# G203B.net
KiCad netlist of a schematic drawn in EAGLE
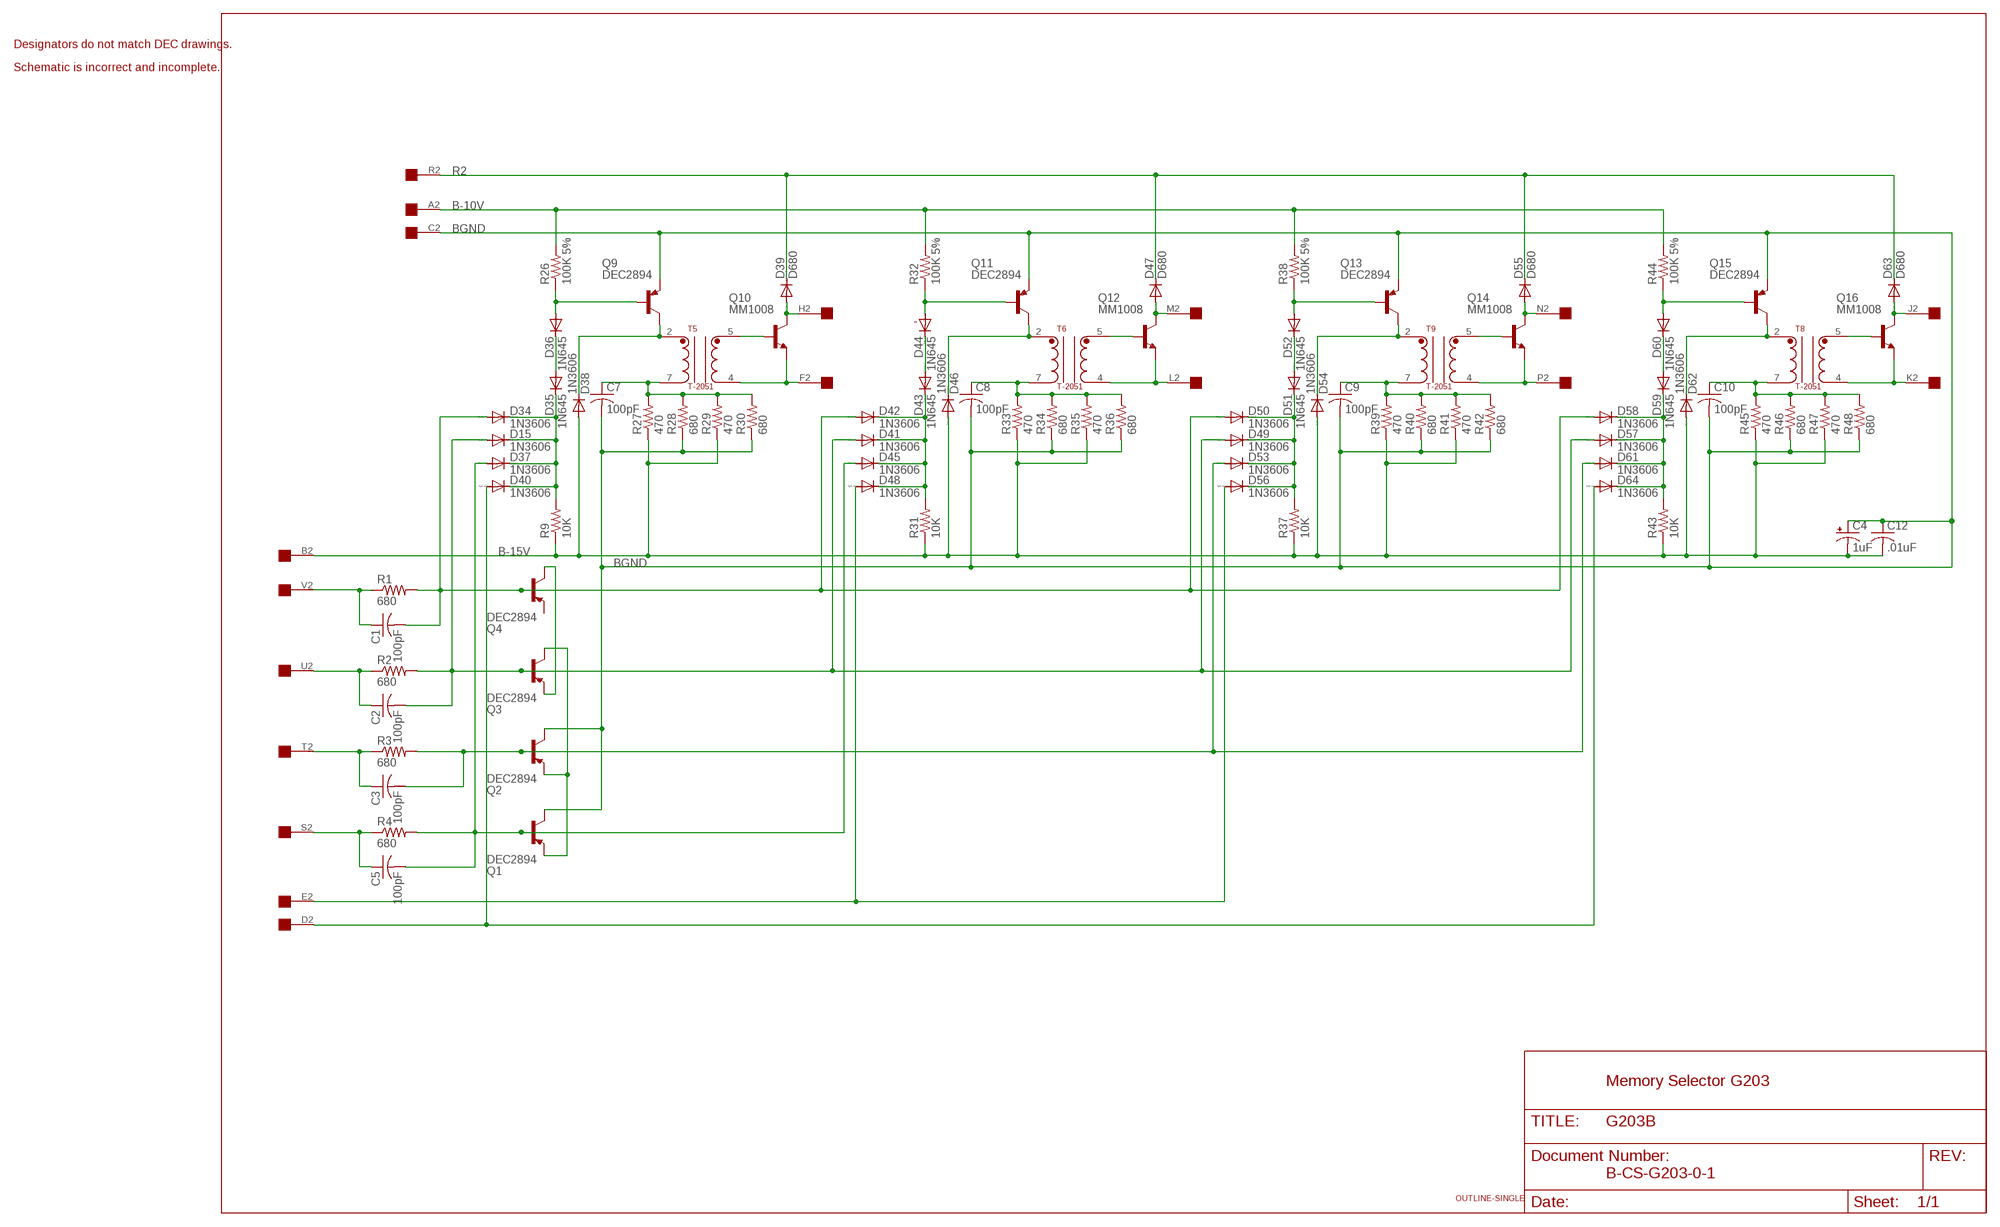
[diagram p0: schematic, sheet 1]

(export (version "E")
  (design (tool "Eeschema 10.0.6"))
  (components
    (comp (ref "C1")
      (value "100pF")
      (footprint "eagle-import:C075-032X103")
      (libsource (lib "eagle-import") (part "C-US075-032X103"))
    )
    (comp (ref "C2")
      (value "100pF")
      (footprint "eagle-import:C075-032X103")
      (libsource (lib "eagle-import") (part "C-US075-032X103"))
    )
    (comp (ref "C3")
      (value "100pF")
      (footprint "eagle-import:C075-032X103")
      (libsource (lib "eagle-import") (part "C-US075-032X103"))
    )
    (comp (ref "C4")
      (value "1uF")
      (footprint "eagle-import:E12-4")
      (libsource (lib "eagle-import") (part "CPOL-USE12-4AXIAL"))
    )
    (comp (ref "C5")
      (value "100pF")
      (footprint "eagle-import:C075-032X103")
      (libsource (lib "eagle-import") (part "C-US075-032X103"))
    )
    (comp (ref "C7")
      (value "100pF")
      (footprint "eagle-import:C075-032X103")
      (libsource (lib "eagle-import") (part "C-US075-032X103"))
    )
    (comp (ref "C8")
      (value "100pF")
      (footprint "eagle-import:C075-032X103")
      (libsource (lib "eagle-import") (part "C-US075-032X103"))
    )
    (comp (ref "C9")
      (value "100pF")
      (footprint "eagle-import:C075-032X103")
      (libsource (lib "eagle-import") (part "C-US075-032X103"))
    )
    (comp (ref "C10")
      (value "100pF")
      (footprint "eagle-import:C075-032X103")
      (libsource (lib "eagle-import") (part "C-US075-032X103"))
    )
    (comp (ref "C12")
      (value ".01uF")
      (footprint "eagle-import:C050-025X075")
      (libsource (lib "eagle-import") (part "C-US050-025X075"))
    )
    (comp (ref "D15")
      (value "1N3606")
      (footprint "eagle-import:DO35-10")
      (libsource (lib "eagle-import") (part "1N4148DO35-10"))
    )
    (comp (ref "D34")
      (value "1N3606")
      (footprint "eagle-import:DO35-10")
      (libsource (lib "eagle-import") (part "1N4148DO35-10"))
    )
    (comp (ref "D35")
      (value "1N645")
      (footprint "eagle-import:DO35-10")
      (libsource (lib "eagle-import") (part "1N4148DO35-10"))
    )
    (comp (ref "D36")
      (value "1N645")
      (footprint "eagle-import:DO35-10")
      (libsource (lib "eagle-import") (part "1N4148DO35-10"))
    )
    (comp (ref "D37")
      (value "1N3606")
      (footprint "eagle-import:DO35-10")
      (libsource (lib "eagle-import") (part "1N4148DO35-10"))
    )
    (comp (ref "D38")
      (value "1N3606")
      (footprint "eagle-import:DO35-10")
      (libsource (lib "eagle-import") (part "1N4148DO35-10"))
    )
    (comp (ref "D39")
      (value "D680")
      (footprint "eagle-import:DO35-10")
      (libsource (lib "eagle-import") (part "1N4148DO35-10"))
    )
    (comp (ref "D40")
      (value "1N3606")
      (footprint "eagle-import:DO35-10")
      (libsource (lib "eagle-import") (part "1N4148DO35-10"))
    )
    (comp (ref "D41")
      (value "1N3606")
      (footprint "eagle-import:DO35-10")
      (libsource (lib "eagle-import") (part "1N4148DO35-10"))
    )
    (comp (ref "D42")
      (value "1N3606")
      (footprint "eagle-import:DO35-10")
      (libsource (lib "eagle-import") (part "1N4148DO35-10"))
    )
    (comp (ref "D43")
      (value "1N645")
      (footprint "eagle-import:DO35-10")
      (libsource (lib "eagle-import") (part "1N4148DO35-10"))
    )
    (comp (ref "D44")
      (value "1N645")
      (footprint "eagle-import:DO35-10")
      (libsource (lib "eagle-import") (part "1N4148DO35-10"))
    )
    (comp (ref "D45")
      (value "1N3606")
      (footprint "eagle-import:DO35-10")
      (libsource (lib "eagle-import") (part "1N4148DO35-10"))
    )
    (comp (ref "D46")
      (value "1N3606")
      (footprint "eagle-import:DO35-10")
      (libsource (lib "eagle-import") (part "1N4148DO35-10"))
    )
    (comp (ref "D47")
      (value "D680")
      (footprint "eagle-import:DO35-10")
      (libsource (lib "eagle-import") (part "1N4148DO35-10"))
    )
    (comp (ref "D48")
      (value "1N3606")
      (footprint "eagle-import:DO35-10")
      (libsource (lib "eagle-import") (part "1N4148DO35-10"))
    )
    (comp (ref "D49")
      (value "1N3606")
      (footprint "eagle-import:DO35-10")
      (libsource (lib "eagle-import") (part "1N4148DO35-10"))
    )
    (comp (ref "D50")
      (value "1N3606")
      (footprint "eagle-import:DO35-10")
      (libsource (lib "eagle-import") (part "1N4148DO35-10"))
    )
    (comp (ref "D51")
      (value "1N645")
      (footprint "eagle-import:DO35-10")
      (libsource (lib "eagle-import") (part "1N4148DO35-10"))
    )
    (comp (ref "D52")
      (value "1N645")
      (footprint "eagle-import:DO35-10")
      (libsource (lib "eagle-import") (part "1N4148DO35-10"))
    )
    (comp (ref "D53")
      (value "1N3606")
      (footprint "eagle-import:DO35-10")
      (libsource (lib "eagle-import") (part "1N4148DO35-10"))
    )
    (comp (ref "D54")
      (value "1N3606")
      (footprint "eagle-import:DO35-10")
      (libsource (lib "eagle-import") (part "1N4148DO35-10"))
    )
    (comp (ref "D55")
      (value "D680")
      (footprint "eagle-import:DO35-10")
      (libsource (lib "eagle-import") (part "1N4148DO35-10"))
    )
    (comp (ref "D56")
      (value "1N3606")
      (footprint "eagle-import:DO35-10")
      (libsource (lib "eagle-import") (part "1N4148DO35-10"))
    )
    (comp (ref "D57")
      (value "1N3606")
      (footprint "eagle-import:DO35-10")
      (libsource (lib "eagle-import") (part "1N4148DO35-10"))
    )
    (comp (ref "D58")
      (value "1N3606")
      (footprint "eagle-import:DO35-10")
      (libsource (lib "eagle-import") (part "1N4148DO35-10"))
    )
    (comp (ref "D59")
      (value "1N645")
      (footprint "eagle-import:DO35-10")
      (libsource (lib "eagle-import") (part "1N4148DO35-10"))
    )
    (comp (ref "D60")
      (value "1N645")
      (footprint "eagle-import:DO35-10")
      (libsource (lib "eagle-import") (part "1N4148DO35-10"))
    )
    (comp (ref "D61")
      (value "1N3606")
      (footprint "eagle-import:DO35-10")
      (libsource (lib "eagle-import") (part "1N4148DO35-10"))
    )
    (comp (ref "D62")
      (value "1N3606")
      (footprint "eagle-import:DO35-10")
      (libsource (lib "eagle-import") (part "1N4148DO35-10"))
    )
    (comp (ref "D63")
      (value "D680")
      (footprint "eagle-import:DO35-10")
      (libsource (lib "eagle-import") (part "1N4148DO35-10"))
    )
    (comp (ref "D64")
      (value "1N3606")
      (footprint "eagle-import:DO35-10")
      (libsource (lib "eagle-import") (part "1N4148DO35-10"))
    )
    (comp (ref "Q1")
      (value "DEC2894")
      (footprint "eagle-import:TO39")
      (libsource (lib "eagle-import") (part "2N2904"))
    )
    (comp (ref "Q2")
      (value "DEC2894")
      (footprint "eagle-import:TO39")
      (libsource (lib "eagle-import") (part "2N2904"))
    )
    (comp (ref "Q3")
      (value "DEC2894")
      (footprint "eagle-import:TO39")
      (libsource (lib "eagle-import") (part "2N2904"))
    )
    (comp (ref "Q4")
      (value "DEC2894")
      (footprint "eagle-import:TO39")
      (libsource (lib "eagle-import") (part "2N2904"))
    )
    (comp (ref "Q9")
      (value "DEC2894")
      (footprint "eagle-import:TO39")
      (libsource (lib "eagle-import") (part "2N2904"))
    )
    (comp (ref "Q10")
      (value "MM1008")
      (footprint "eagle-import:TO5")
      (libsource (lib "eagle-import") (part "2N2102"))
    )
    (comp (ref "Q11")
      (value "DEC2894")
      (footprint "eagle-import:TO39")
      (libsource (lib "eagle-import") (part "2N2904"))
    )
    (comp (ref "Q12")
      (value "MM1008")
      (footprint "eagle-import:TO5")
      (libsource (lib "eagle-import") (part "2N2102"))
    )
    (comp (ref "Q13")
      (value "DEC2894")
      (footprint "eagle-import:TO39")
      (libsource (lib "eagle-import") (part "2N2904"))
    )
    (comp (ref "Q14")
      (value "MM1008")
      (footprint "eagle-import:TO5")
      (libsource (lib "eagle-import") (part "2N2102"))
    )
    (comp (ref "Q15")
      (value "DEC2894")
      (footprint "eagle-import:TO39")
      (libsource (lib "eagle-import") (part "2N2904"))
    )
    (comp (ref "Q16")
      (value "MM1008")
      (footprint "eagle-import:TO5")
      (libsource (lib "eagle-import") (part "2N2102"))
    )
    (comp (ref "R1")
      (value "680")
      (footprint "eagle-import:0207_10")
      (libsource (lib "eagle-import") (part "R-US_0207/10"))
    )
    (comp (ref "R2")
      (value "680")
      (footprint "eagle-import:0207_10")
      (libsource (lib "eagle-import") (part "R-US_0207/10"))
    )
    (comp (ref "R3")
      (value "680")
      (footprint "eagle-import:0207_10")
      (libsource (lib "eagle-import") (part "R-US_0207/10"))
    )
    (comp (ref "R4")
      (value "680")
      (footprint "eagle-import:0207_10")
      (libsource (lib "eagle-import") (part "R-US_0207/10"))
    )
    (comp (ref "R9")
      (value "10K")
      (footprint "eagle-import:0207_10")
      (libsource (lib "eagle-import") (part "R-US_0207/10"))
    )
    (comp (ref "R26")
      (value "100K 5%")
      (footprint "eagle-import:0207_10")
      (libsource (lib "eagle-import") (part "R-US_0207/10"))
    )
    (comp (ref "R27")
      (value "470")
      (footprint "eagle-import:0207_10")
      (libsource (lib "eagle-import") (part "R-US_0207/10"))
    )
    (comp (ref "R28")
      (value "680")
      (footprint "eagle-import:0207_10")
      (libsource (lib "eagle-import") (part "R-US_0207/10"))
    )
    (comp (ref "R29")
      (value "470")
      (footprint "eagle-import:0207_10")
      (libsource (lib "eagle-import") (part "R-US_0207/10"))
    )
    (comp (ref "R30")
      (value "680")
      (footprint "eagle-import:0207_10")
      (libsource (lib "eagle-import") (part "R-US_0207/10"))
    )
    (comp (ref "R31")
      (value "10K")
      (footprint "eagle-import:0207_10")
      (libsource (lib "eagle-import") (part "R-US_0207/10"))
    )
    (comp (ref "R32")
      (value "100K 5%")
      (footprint "eagle-import:0207_10")
      (libsource (lib "eagle-import") (part "R-US_0207/10"))
    )
    (comp (ref "R33")
      (value "470")
      (footprint "eagle-import:0207_10")
      (libsource (lib "eagle-import") (part "R-US_0207/10"))
    )
    (comp (ref "R34")
      (value "680")
      (footprint "eagle-import:0207_10")
      (libsource (lib "eagle-import") (part "R-US_0207/10"))
    )
    (comp (ref "R35")
      (value "470")
      (footprint "eagle-import:0207_10")
      (libsource (lib "eagle-import") (part "R-US_0207/10"))
    )
    (comp (ref "R36")
      (value "680")
      (footprint "eagle-import:0207_10")
      (libsource (lib "eagle-import") (part "R-US_0207/10"))
    )
    (comp (ref "R37")
      (value "10K")
      (footprint "eagle-import:0207_10")
      (libsource (lib "eagle-import") (part "R-US_0207/10"))
    )
    (comp (ref "R38")
      (value "100K 5%")
      (footprint "eagle-import:0207_10")
      (libsource (lib "eagle-import") (part "R-US_0207/10"))
    )
    (comp (ref "R39")
      (value "470")
      (footprint "eagle-import:0207_10")
      (libsource (lib "eagle-import") (part "R-US_0207/10"))
    )
    (comp (ref "R40")
      (value "680")
      (footprint "eagle-import:0207_10")
      (libsource (lib "eagle-import") (part "R-US_0207/10"))
    )
    (comp (ref "R41")
      (value "470")
      (footprint "eagle-import:0207_10")
      (libsource (lib "eagle-import") (part "R-US_0207/10"))
    )
    (comp (ref "R42")
      (value "680")
      (footprint "eagle-import:0207_10")
      (libsource (lib "eagle-import") (part "R-US_0207/10"))
    )
    (comp (ref "R43")
      (value "10K")
      (footprint "eagle-import:0207_10")
      (libsource (lib "eagle-import") (part "R-US_0207/10"))
    )
    (comp (ref "R44")
      (value "100K 5%")
      (footprint "eagle-import:0207_10")
      (libsource (lib "eagle-import") (part "R-US_0207/10"))
    )
    (comp (ref "R45")
      (value "470")
      (footprint "eagle-import:0207_10")
      (libsource (lib "eagle-import") (part "R-US_0207/10"))
    )
    (comp (ref "R46")
      (value "680")
      (footprint "eagle-import:0207_10")
      (libsource (lib "eagle-import") (part "R-US_0207/10"))
    )
    (comp (ref "R47")
      (value "470")
      (footprint "eagle-import:0207_10")
      (libsource (lib "eagle-import") (part "R-US_0207/10"))
    )
    (comp (ref "R48")
      (value "680")
      (footprint "eagle-import:0207_10")
      (libsource (lib "eagle-import") (part "R-US_0207/10"))
    )
    (comp (ref "T5")
      (value "T-2051")
      (footprint "eagle-import:TRANSFORMER")
      (libsource (lib "eagle-import") (part "T-2051"))
    )
    (comp (ref "T6")
      (value "T-2051")
      (footprint "eagle-import:TRANSFORMER")
      (libsource (lib "eagle-import") (part "T-2051"))
    )
    (comp (ref "T8")
      (value "T-2051")
      (footprint "eagle-import:TRANSFORMER")
      (libsource (lib "eagle-import") (part "T-2051"))
    )
    (comp (ref "T9")
      (value "T-2051")
      (footprint "eagle-import:TRANSFORMER")
      (libsource (lib "eagle-import") (part "T-2051"))
    )
    (comp (ref "U$1")
      (value "OUTLINE-SINGLE")
      (footprint "eagle-import:SINGLE")
      (libsource (lib "eagle-import") (part "OUTLINE-SINGLE"))
    )
    (comp (ref "U$2")
      (value "EDGE-1")
      (footprint "eagle-import:EDGE-CON1")
      (libsource (lib "eagle-import") (part "EDGE-1"))
    )
  )
  (nets
    (net (code "1") (name "/B-10V") (class "Default")
      (node (ref "R26") (pin "2") (pinfunction "2_2") (pintype "passive"))
      (node (ref "R32") (pin "2") (pinfunction "2_2") (pintype "passive"))
      (node (ref "R38") (pin "2") (pinfunction "2_2") (pintype "passive"))
      (node (ref "R44") (pin "2") (pinfunction "2_2") (pintype "passive"))
      (node (ref "U$2") (pin "A2") (pinfunction "1_A2") (pintype "bidirectional"))
    )
    (net (code "2") (name "/B-15V") (class "Default")
      (node (ref "C12") (pin "2") (pinfunction "2_2") (pintype "passive"))
      (node (ref "C4") (pin "-") (pinfunction "-_-") (pintype "passive"))
      (node (ref "D38") (pin "A") (pinfunction "A_A") (pintype "passive"))
      (node (ref "D46") (pin "A") (pinfunction "A_A") (pintype "passive"))
      (node (ref "D54") (pin "A") (pinfunction "A_A") (pintype "passive"))
      (node (ref "D62") (pin "A") (pinfunction "A_A") (pintype "passive"))
      (node (ref "R27") (pin "1") (pinfunction "1_1") (pintype "passive"))
      (node (ref "R29") (pin "1") (pinfunction "1_1") (pintype "passive"))
      (node (ref "R31") (pin "1") (pinfunction "1_1") (pintype "passive"))
      (node (ref "R33") (pin "1") (pinfunction "1_1") (pintype "passive"))
      (node (ref "R35") (pin "1") (pinfunction "1_1") (pintype "passive"))
      (node (ref "R37") (pin "1") (pinfunction "1_1") (pintype "passive"))
      (node (ref "R39") (pin "1") (pinfunction "1_1") (pintype "passive"))
      (node (ref "R41") (pin "1") (pinfunction "1_1") (pintype "passive"))
      (node (ref "R43") (pin "1") (pinfunction "1_1") (pintype "passive"))
      (node (ref "R45") (pin "1") (pinfunction "1_1") (pintype "passive"))
      (node (ref "R47") (pin "1") (pinfunction "1_1") (pintype "passive"))
      (node (ref "R9") (pin "1") (pinfunction "1_1") (pintype "passive"))
      (node (ref "U$2") (pin "B2") (pinfunction "1_B2") (pintype "bidirectional"))
    )
    (net (code "3") (name "/BGND") (class "Default")
      (node (ref "C10") (pin "2") (pinfunction "2_2") (pintype "passive"))
      (node (ref "C12") (pin "1") (pinfunction "1_1") (pintype "passive"))
      (node (ref "C4") (pin "+") (pinfunction "+_+") (pintype "passive"))
      (node (ref "C7") (pin "2") (pinfunction "2_2") (pintype "passive"))
      (node (ref "C8") (pin "2") (pinfunction "2_2") (pintype "passive"))
      (node (ref "C9") (pin "2") (pinfunction "2_2") (pintype "passive"))
      (node (ref "Q1") (pin "3") (pinfunction "C_3") (pintype "passive"))
      (node (ref "Q11") (pin "1") (pinfunction "E_1") (pintype "passive"))
      (node (ref "Q13") (pin "1") (pinfunction "E_1") (pintype "passive"))
      (node (ref "Q15") (pin "1") (pinfunction "E_1") (pintype "passive"))
      (node (ref "Q2") (pin "3") (pinfunction "C_3") (pintype "passive"))
      (node (ref "Q9") (pin "1") (pinfunction "E_1") (pintype "passive"))
      (node (ref "R28") (pin "1") (pinfunction "1_1") (pintype "passive"))
      (node (ref "R30") (pin "1") (pinfunction "1_1") (pintype "passive"))
      (node (ref "R34") (pin "1") (pinfunction "1_1") (pintype "passive"))
      (node (ref "R36") (pin "1") (pinfunction "1_1") (pintype "passive"))
      (node (ref "R40") (pin "1") (pinfunction "1_1") (pintype "passive"))
      (node (ref "R42") (pin "1") (pinfunction "1_1") (pintype "passive"))
      (node (ref "R46") (pin "1") (pinfunction "1_1") (pintype "passive"))
      (node (ref "R48") (pin "1") (pinfunction "1_1") (pintype "passive"))
      (node (ref "U$2") (pin "C2") (pinfunction "1_C2") (pintype "bidirectional"))
    )
    (net (code "4") (name "/R2") (class "Default")
      (node (ref "D39") (pin "C") (pinfunction "C_C") (pintype "passive"))
      (node (ref "D47") (pin "C") (pinfunction "C_C") (pintype "passive"))
      (node (ref "D55") (pin "C") (pinfunction "C_C") (pintype "passive"))
      (node (ref "D63") (pin "C") (pinfunction "C_C") (pintype "passive"))
      (node (ref "U$2") (pin "R2") (pinfunction "1_R2") (pintype "bidirectional"))
    )
    (net (code "5") (name "Net-(D15-PadC)") (class "Default")
      (node (ref "D15") (pin "C") (pinfunction "C_C") (pintype "passive"))
      (node (ref "D34") (pin "C") (pinfunction "C_C") (pintype "passive"))
      (node (ref "D35") (pin "C") (pinfunction "C_C") (pintype "passive"))
      (node (ref "D37") (pin "C") (pinfunction "C_C") (pintype "passive"))
      (node (ref "D40") (pin "C") (pinfunction "C_C") (pintype "passive"))
      (node (ref "R9") (pin "2") (pinfunction "2_2") (pintype "passive"))
    )
    (net (code "6") (name "Net-(D35-PadA)") (class "Default")
      (node (ref "D35") (pin "A") (pinfunction "A_A") (pintype "passive"))
      (node (ref "D36") (pin "C") (pinfunction "C_C") (pintype "passive"))
    )
    (net (code "7") (name "Net-(D41-PadC)") (class "Default")
      (node (ref "D41") (pin "C") (pinfunction "C_C") (pintype "passive"))
      (node (ref "D42") (pin "C") (pinfunction "C_C") (pintype "passive"))
      (node (ref "D43") (pin "C") (pinfunction "C_C") (pintype "passive"))
      (node (ref "D45") (pin "C") (pinfunction "C_C") (pintype "passive"))
      (node (ref "D48") (pin "C") (pinfunction "C_C") (pintype "passive"))
      (node (ref "R31") (pin "2") (pinfunction "2_2") (pintype "passive"))
    )
    (net (code "8") (name "Net-(D43-PadA)") (class "Default")
      (node (ref "D43") (pin "A") (pinfunction "A_A") (pintype "passive"))
      (node (ref "D44") (pin "C") (pinfunction "C_C") (pintype "passive"))
    )
    (net (code "9") (name "Net-(D49-PadC)") (class "Default")
      (node (ref "D49") (pin "C") (pinfunction "C_C") (pintype "passive"))
      (node (ref "D50") (pin "C") (pinfunction "C_C") (pintype "passive"))
      (node (ref "D51") (pin "C") (pinfunction "C_C") (pintype "passive"))
      (node (ref "D53") (pin "C") (pinfunction "C_C") (pintype "passive"))
      (node (ref "D56") (pin "C") (pinfunction "C_C") (pintype "passive"))
      (node (ref "R37") (pin "2") (pinfunction "2_2") (pintype "passive"))
    )
    (net (code "10") (name "Net-(D51-PadA)") (class "Default")
      (node (ref "D51") (pin "A") (pinfunction "A_A") (pintype "passive"))
      (node (ref "D52") (pin "C") (pinfunction "C_C") (pintype "passive"))
    )
    (net (code "11") (name "Net-(D57-PadC)") (class "Default")
      (node (ref "D57") (pin "C") (pinfunction "C_C") (pintype "passive"))
      (node (ref "D58") (pin "C") (pinfunction "C_C") (pintype "passive"))
      (node (ref "D59") (pin "C") (pinfunction "C_C") (pintype "passive"))
      (node (ref "D61") (pin "C") (pinfunction "C_C") (pintype "passive"))
      (node (ref "D64") (pin "C") (pinfunction "C_C") (pintype "passive"))
      (node (ref "R43") (pin "2") (pinfunction "2_2") (pintype "passive"))
    )
    (net (code "12") (name "Net-(D59-PadA)") (class "Default")
      (node (ref "D59") (pin "A") (pinfunction "A_A") (pintype "passive"))
      (node (ref "D60") (pin "C") (pinfunction "C_C") (pintype "passive"))
    )
    (net (code "13") (name "Net-(Q1-B)") (class "Default")
      (node (ref "C5") (pin "2") (pinfunction "2_2") (pintype "passive"))
      (node (ref "D37") (pin "A") (pinfunction "A_A") (pintype "passive"))
      (node (ref "D45") (pin "A") (pinfunction "A_A") (pintype "passive"))
      (node (ref "Q1") (pin "2") (pinfunction "B_2") (pintype "passive"))
      (node (ref "R4") (pin "2") (pinfunction "2_2") (pintype "passive"))
    )
    (net (code "14") (name "Net-(Q1-E)") (class "Default")
      (node (ref "Q1") (pin "1") (pinfunction "E_1") (pintype "passive"))
      (node (ref "Q2") (pin "1") (pinfunction "E_1") (pintype "passive"))
      (node (ref "Q3") (pin "3") (pinfunction "C_3") (pintype "passive"))
    )
    (net (code "15") (name "Net-(Q2-B)") (class "Default")
      (node (ref "C3") (pin "2") (pinfunction "2_2") (pintype "passive"))
      (node (ref "D53") (pin "A") (pinfunction "A_A") (pintype "passive"))
      (node (ref "D61") (pin "A") (pinfunction "A_A") (pintype "passive"))
      (node (ref "Q2") (pin "2") (pinfunction "B_2") (pintype "passive"))
      (node (ref "R3") (pin "2") (pinfunction "2_2") (pintype "passive"))
    )
    (net (code "16") (name "Net-(Q3-B)") (class "Default")
      (node (ref "C2") (pin "2") (pinfunction "2_2") (pintype "passive"))
      (node (ref "D15") (pin "A") (pinfunction "A_A") (pintype "passive"))
      (node (ref "D41") (pin "A") (pinfunction "A_A") (pintype "passive"))
      (node (ref "D49") (pin "A") (pinfunction "A_A") (pintype "passive"))
      (node (ref "D57") (pin "A") (pinfunction "A_A") (pintype "passive"))
      (node (ref "Q3") (pin "2") (pinfunction "B_2") (pintype "passive"))
      (node (ref "R2") (pin "2") (pinfunction "2_2") (pintype "passive"))
    )
    (net (code "17") (name "Net-(Q3-E)") (class "Default")
      (node (ref "Q3") (pin "1") (pinfunction "E_1") (pintype "passive"))
      (node (ref "Q4") (pin "3") (pinfunction "C_3") (pintype "passive"))
    )
    (net (code "18") (name "Net-(Q4-B)") (class "Default")
      (node (ref "C1") (pin "2") (pinfunction "2_2") (pintype "passive"))
      (node (ref "D34") (pin "A") (pinfunction "A_A") (pintype "passive"))
      (node (ref "D42") (pin "A") (pinfunction "A_A") (pintype "passive"))
      (node (ref "D50") (pin "A") (pinfunction "A_A") (pintype "passive"))
      (node (ref "D58") (pin "A") (pinfunction "A_A") (pintype "passive"))
      (node (ref "Q4") (pin "2") (pinfunction "B_2") (pintype "passive"))
      (node (ref "R1") (pin "2") (pinfunction "2_2") (pintype "passive"))
    )
    (net (code "19") (name "Net-(Q9-B)") (class "Default")
      (node (ref "D36") (pin "A") (pinfunction "A_A") (pintype "passive"))
      (node (ref "Q9") (pin "2") (pinfunction "B_2") (pintype "passive"))
      (node (ref "R26") (pin "1") (pinfunction "1_1") (pintype "passive"))
    )
    (net (code "20") (name "Net-(Q9-C)") (class "Default")
      (node (ref "D38") (pin "C") (pinfunction "C_C") (pintype "passive"))
      (node (ref "Q9") (pin "3") (pinfunction "C_3") (pintype "passive"))
      (node (ref "T5") (pin "2") (pinfunction "P$2_2") (pintype "passive"))
    )
    (net (code "21") (name "Net-(Q10-B)") (class "Default")
      (node (ref "Q10") (pin "2") (pinfunction "B_2") (pintype "passive"))
      (node (ref "T5") (pin "5") (pinfunction "P$4_5") (pintype "passive"))
    )
    (net (code "22") (name "Net-(Q10-C)") (class "Default")
      (node (ref "D39") (pin "A") (pinfunction "A_A") (pintype "passive"))
      (node (ref "Q10") (pin "3") (pinfunction "C_3") (pintype "passive"))
      (node (ref "U$2") (pin "H2") (pinfunction "1_H2") (pintype "bidirectional"))
    )
    (net (code "23") (name "Net-(Q10-E)") (class "Default")
      (node (ref "Q10") (pin "1") (pinfunction "E_1") (pintype "passive"))
      (node (ref "T5") (pin "4") (pinfunction "P$5_4") (pintype "passive"))
      (node (ref "U$2") (pin "F2") (pinfunction "1_F2") (pintype "bidirectional"))
    )
    (net (code "24") (name "Net-(Q11-B)") (class "Default")
      (node (ref "D44") (pin "A") (pinfunction "A_A") (pintype "passive"))
      (node (ref "Q11") (pin "2") (pinfunction "B_2") (pintype "passive"))
      (node (ref "R32") (pin "1") (pinfunction "1_1") (pintype "passive"))
    )
    (net (code "25") (name "Net-(Q11-C)") (class "Default")
      (node (ref "D46") (pin "C") (pinfunction "C_C") (pintype "passive"))
      (node (ref "Q11") (pin "3") (pinfunction "C_3") (pintype "passive"))
      (node (ref "T6") (pin "2") (pinfunction "P$2_2") (pintype "passive"))
    )
    (net (code "26") (name "Net-(Q12-B)") (class "Default")
      (node (ref "Q12") (pin "2") (pinfunction "B_2") (pintype "passive"))
      (node (ref "T6") (pin "5") (pinfunction "P$4_5") (pintype "passive"))
    )
    (net (code "27") (name "Net-(Q12-C)") (class "Default")
      (node (ref "D47") (pin "A") (pinfunction "A_A") (pintype "passive"))
      (node (ref "Q12") (pin "3") (pinfunction "C_3") (pintype "passive"))
      (node (ref "U$2") (pin "M2") (pinfunction "1_M2") (pintype "bidirectional"))
    )
    (net (code "28") (name "Net-(Q12-E)") (class "Default")
      (node (ref "Q12") (pin "1") (pinfunction "E_1") (pintype "passive"))
      (node (ref "T6") (pin "4") (pinfunction "P$5_4") (pintype "passive"))
      (node (ref "U$2") (pin "L2") (pinfunction "1_L2") (pintype "bidirectional"))
    )
    (net (code "29") (name "Net-(Q13-B)") (class "Default")
      (node (ref "D52") (pin "A") (pinfunction "A_A") (pintype "passive"))
      (node (ref "Q13") (pin "2") (pinfunction "B_2") (pintype "passive"))
      (node (ref "R38") (pin "1") (pinfunction "1_1") (pintype "passive"))
    )
    (net (code "30") (name "Net-(Q13-C)") (class "Default")
      (node (ref "D54") (pin "C") (pinfunction "C_C") (pintype "passive"))
      (node (ref "Q13") (pin "3") (pinfunction "C_3") (pintype "passive"))
      (node (ref "T9") (pin "2") (pinfunction "P$2_2") (pintype "passive"))
    )
    (net (code "31") (name "Net-(Q14-B)") (class "Default")
      (node (ref "Q14") (pin "2") (pinfunction "B_2") (pintype "passive"))
      (node (ref "T9") (pin "5") (pinfunction "P$4_5") (pintype "passive"))
    )
    (net (code "32") (name "Net-(Q14-C)") (class "Default")
      (node (ref "D55") (pin "A") (pinfunction "A_A") (pintype "passive"))
      (node (ref "Q14") (pin "3") (pinfunction "C_3") (pintype "passive"))
      (node (ref "U$2") (pin "N2") (pinfunction "1_N2") (pintype "bidirectional"))
    )
    (net (code "33") (name "Net-(Q14-E)") (class "Default")
      (node (ref "Q14") (pin "1") (pinfunction "E_1") (pintype "passive"))
      (node (ref "T9") (pin "4") (pinfunction "P$5_4") (pintype "passive"))
      (node (ref "U$2") (pin "P2") (pinfunction "1_P2") (pintype "bidirectional"))
    )
    (net (code "34") (name "Net-(Q15-B)") (class "Default")
      (node (ref "D60") (pin "A") (pinfunction "A_A") (pintype "passive"))
      (node (ref "Q15") (pin "2") (pinfunction "B_2") (pintype "passive"))
      (node (ref "R44") (pin "1") (pinfunction "1_1") (pintype "passive"))
    )
    (net (code "35") (name "Net-(Q15-C)") (class "Default")
      (node (ref "D62") (pin "C") (pinfunction "C_C") (pintype "passive"))
      (node (ref "Q15") (pin "3") (pinfunction "C_3") (pintype "passive"))
      (node (ref "T8") (pin "2") (pinfunction "P$2_2") (pintype "passive"))
    )
    (net (code "36") (name "Net-(Q16-B)") (class "Default")
      (node (ref "Q16") (pin "2") (pinfunction "B_2") (pintype "passive"))
      (node (ref "T8") (pin "5") (pinfunction "P$4_5") (pintype "passive"))
    )
    (net (code "37") (name "Net-(Q16-C)") (class "Default")
      (node (ref "D63") (pin "A") (pinfunction "A_A") (pintype "passive"))
      (node (ref "Q16") (pin "3") (pinfunction "C_3") (pintype "passive"))
      (node (ref "U$2") (pin "J2") (pinfunction "1_J2") (pintype "bidirectional"))
    )
    (net (code "38") (name "Net-(Q16-E)") (class "Default")
      (node (ref "Q16") (pin "1") (pinfunction "E_1") (pintype "passive"))
      (node (ref "T8") (pin "4") (pinfunction "P$5_4") (pintype "passive"))
      (node (ref "U$2") (pin "K2") (pinfunction "1_K2") (pintype "bidirectional"))
    )
    (net (code "39") (name "Net-(T5-P$7)") (class "Default")
      (node (ref "C7") (pin "1") (pinfunction "1_1") (pintype "passive"))
      (node (ref "R27") (pin "2") (pinfunction "2_2") (pintype "passive"))
      (node (ref "R28") (pin "2") (pinfunction "2_2") (pintype "passive"))
      (node (ref "R29") (pin "2") (pinfunction "2_2") (pintype "passive"))
      (node (ref "R30") (pin "2") (pinfunction "2_2") (pintype "passive"))
      (node (ref "T5") (pin "7") (pinfunction "P$7_7") (pintype "passive"))
    )
    (net (code "40") (name "Net-(T6-P$7)") (class "Default")
      (node (ref "C8") (pin "1") (pinfunction "1_1") (pintype "passive"))
      (node (ref "R33") (pin "2") (pinfunction "2_2") (pintype "passive"))
      (node (ref "R34") (pin "2") (pinfunction "2_2") (pintype "passive"))
      (node (ref "R35") (pin "2") (pinfunction "2_2") (pintype "passive"))
      (node (ref "R36") (pin "2") (pinfunction "2_2") (pintype "passive"))
      (node (ref "T6") (pin "7") (pinfunction "P$7_7") (pintype "passive"))
    )
    (net (code "41") (name "Net-(T8-P$7)") (class "Default")
      (node (ref "C10") (pin "1") (pinfunction "1_1") (pintype "passive"))
      (node (ref "R45") (pin "2") (pinfunction "2_2") (pintype "passive"))
      (node (ref "R46") (pin "2") (pinfunction "2_2") (pintype "passive"))
      (node (ref "R47") (pin "2") (pinfunction "2_2") (pintype "passive"))
      (node (ref "R48") (pin "2") (pinfunction "2_2") (pintype "passive"))
      (node (ref "T8") (pin "7") (pinfunction "P$7_7") (pintype "passive"))
    )
    (net (code "42") (name "Net-(T9-P$7)") (class "Default")
      (node (ref "C9") (pin "1") (pinfunction "1_1") (pintype "passive"))
      (node (ref "R39") (pin "2") (pinfunction "2_2") (pintype "passive"))
      (node (ref "R40") (pin "2") (pinfunction "2_2") (pintype "passive"))
      (node (ref "R41") (pin "2") (pinfunction "2_2") (pintype "passive"))
      (node (ref "R42") (pin "2") (pinfunction "2_2") (pintype "passive"))
      (node (ref "T9") (pin "7") (pinfunction "P$7_7") (pintype "passive"))
    )
    (net (code "43") (name "Net-(U$2D-1)") (class "Default")
      (node (ref "D40") (pin "A") (pinfunction "A_A") (pintype "passive"))
      (node (ref "D64") (pin "A") (pinfunction "A_A") (pintype "passive"))
      (node (ref "U$2") (pin "D2") (pinfunction "1_D2") (pintype "bidirectional"))
    )
    (net (code "44") (name "Net-(U$2E-1)") (class "Default")
      (node (ref "D48") (pin "A") (pinfunction "A_A") (pintype "passive"))
      (node (ref "D56") (pin "A") (pinfunction "A_A") (pintype "passive"))
      (node (ref "U$2") (pin "E2") (pinfunction "1_E2") (pintype "bidirectional"))
    )
    (net (code "45") (name "Net-(U$2O-1)") (class "Default")
      (node (ref "C5") (pin "1") (pinfunction "1_1") (pintype "passive"))
      (node (ref "R4") (pin "1") (pinfunction "1_1") (pintype "passive"))
      (node (ref "U$2") (pin "S2") (pinfunction "1_S2") (pintype "bidirectional"))
    )
    (net (code "46") (name "Net-(U$2P-1)") (class "Default")
      (node (ref "C3") (pin "1") (pinfunction "1_1") (pintype "passive"))
      (node (ref "R3") (pin "1") (pinfunction "1_1") (pintype "passive"))
      (node (ref "U$2") (pin "T2") (pinfunction "1_T2") (pintype "bidirectional"))
    )
    (net (code "47") (name "Net-(U$2Q-1)") (class "Default")
      (node (ref "C2") (pin "1") (pinfunction "1_1") (pintype "passive"))
      (node (ref "R2") (pin "1") (pinfunction "1_1") (pintype "passive"))
      (node (ref "U$2") (pin "U2") (pinfunction "1_U2") (pintype "bidirectional"))
    )
    (net (code "48") (name "Net-(U$2R-1)") (class "Default")
      (node (ref "C1") (pin "1") (pinfunction "1_1") (pintype "passive"))
      (node (ref "R1") (pin "1") (pinfunction "1_1") (pintype "passive"))
      (node (ref "U$2") (pin "V2") (pinfunction "1_V2") (pintype "bidirectional"))
    )
    (net (code "49") (name "unconnected-(Q4-E-Pad1)") (class "Default")
      (node (ref "Q4") (pin "1") (pinfunction "E_1") (pintype "passive"))
    )
  )
)
